# Driver_Board_Simplified.net
KiCad netlist of a schematic drawn in Altium Designer
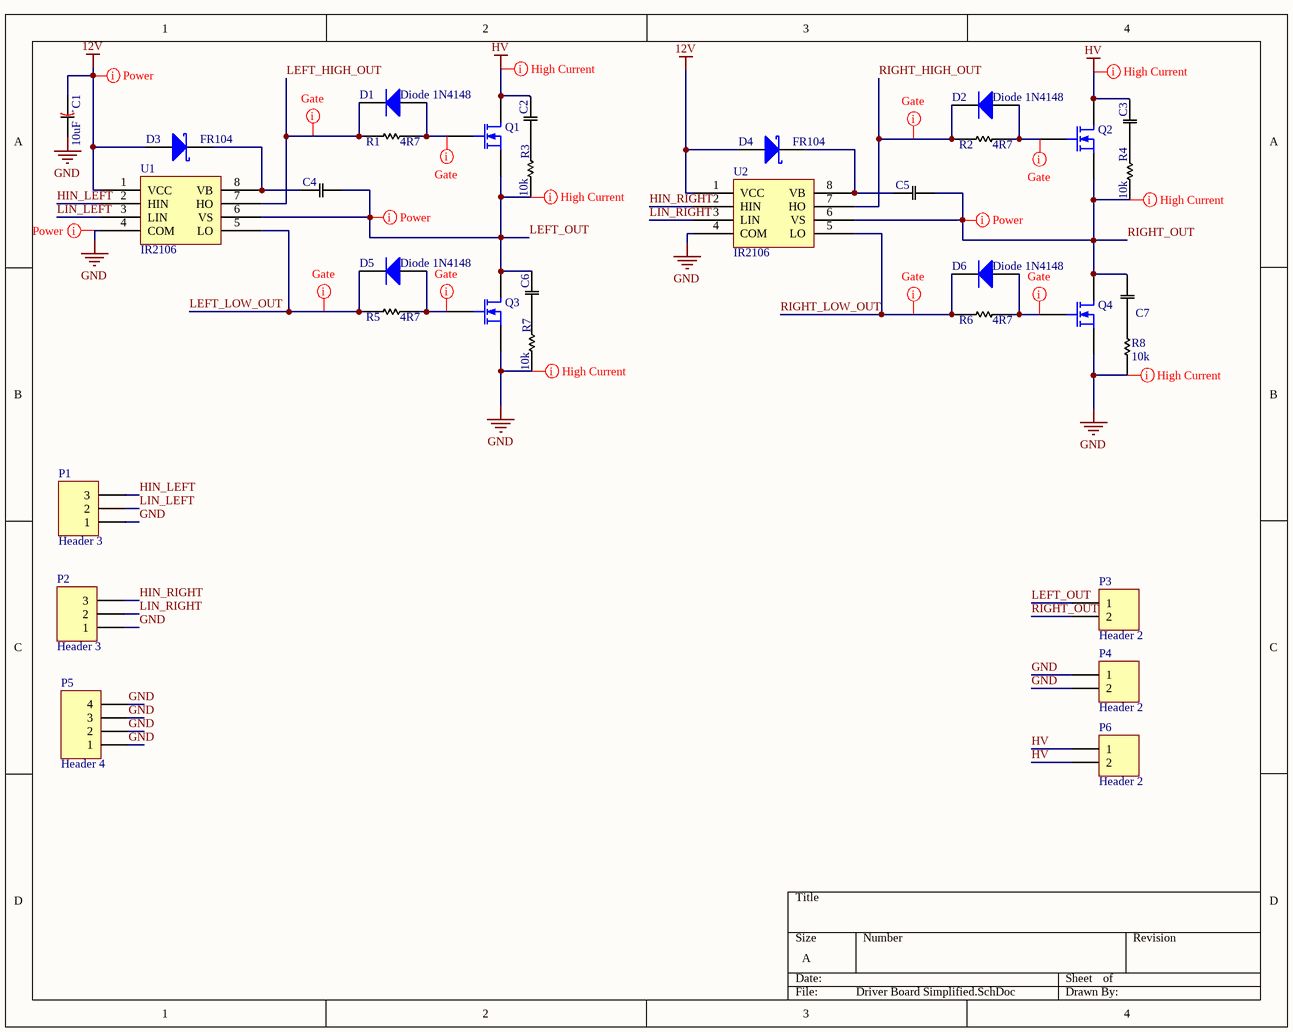
[diagram p0: Driver Board Simplified.SchDoc]

(export (version "E")
  (design (tool "Eeschema 10.0.6"))
  (components
    (comp (ref "C1")
      (value "10uF")
      (footprint "100mil CAP - 80mil pad")
      (libsource (lib "aroshaD") (part "Electrolytic Cap"))
    )
    (comp (ref "C2")
      (value "Ceramic Cap")
      (footprint "6-0805_N")
      (libsource (lib "aroshaD") (part "Ceramic Cap"))
    )
    (comp (ref "C3")
      (value "Ceramic Cap")
      (footprint "6-0805_N")
      (libsource (lib "aroshaD") (part "Ceramic Cap"))
    )
    (comp (ref "C4")
      (value "Ceramic Cap")
      (footprint "6-0805_L")
      (libsource (lib "aroshaD") (part "Ceramic Cap"))
    )
    (comp (ref "C5")
      (value "Ceramic Cap")
      (footprint "6-0805_L")
      (libsource (lib "aroshaD") (part "Ceramic Cap"))
    )
    (comp (ref "C6")
      (value "Ceramic Cap")
      (footprint "6-0805_N")
      (libsource (lib "aroshaD") (part "Ceramic Cap"))
    )
    (comp (ref "C7")
      (value "Ceramic Cap")
      (footprint "6-0805_N")
      (libsource (lib "aroshaD") (part "Ceramic Cap"))
    )
    (comp (ref "D1")
      (value "Diode 1N4148")
      (footprint "Resistor 100MIL")
      (description "High Conductance Fast Diode")
      (fields (field (name "PUBLISHER") "Altium Limited"))
      (libsource (lib "Miscellaneous Devices") (part "Diode 1N4148"))
    )
    (comp (ref "D2")
      (value "Diode 1N4148")
      (footprint "Resistor 100MIL")
      (description "High Conductance Fast Diode")
      (fields (field (name "PUBLISHER") "Altium Limited"))
      (libsource (lib "Miscellaneous Devices") (part "Diode 1N4148"))
    )
    (comp (ref "D3")
      (value "FR104")
      (footprint "DO-35")
      (description "Schottky Rectifier")
      (fields (field (name "PUBLISHER") "Altium Limited"))
      (libsource (lib "Miscellaneous Devices") (part "Diode 11DQ03"))
    )
    (comp (ref "D4")
      (value "FR104")
      (footprint "Resistor 100MIL")
      (description "Schottky Rectifier")
      (fields (field (name "PUBLISHER") "Altium Limited"))
      (libsource (lib "Miscellaneous Devices") (part "Diode 11DQ03"))
    )
    (comp (ref "D5")
      (value "Diode 1N4148")
      (footprint "Resistor 100MIL")
      (description "High Conductance Fast Diode")
      (fields (field (name "PUBLISHER") "Altium Limited"))
      (libsource (lib "Miscellaneous Devices") (part "Diode 1N4148"))
    )
    (comp (ref "D6")
      (value "Diode 1N4148")
      (footprint "Resistor 100MIL")
      (description "High Conductance Fast Diode")
      (fields (field (name "PUBLISHER") "Altium Limited"))
      (libsource (lib "Miscellaneous Devices") (part "Diode 1N4148"))
    )
    (comp (ref "P1")
      (value "Header 3")
      (footprint "HDR1X3")
      (description "Header, 3-Pin")
      (fields (field (name "PUBLISHER") "Altium Limited"))
      (libsource (lib "Miscellaneous Connectors") (part "Header 3"))
    )
    (comp (ref "P2")
      (value "Header 3")
      (footprint "HDR1X3")
      (description "Header, 3-Pin")
      (fields (field (name "PUBLISHER") "Altium Limited"))
      (libsource (lib "Miscellaneous Connectors") (part "Header 3"))
    )
    (comp (ref "P3")
      (value "Header 2")
      (footprint "2P_PCB_TERM_BLOCK_HDR")
      (description "Header, 2-Pin")
      (fields (field (name "PUBLISHER") "Altium Limited"))
      (libsource (lib "Miscellaneous Connectors") (part "Header 2"))
    )
    (comp (ref "P4")
      (value "Header 2")
      (footprint "2P_PCB_TERM_BLOCK_HDR")
      (description "Header, 2-Pin")
      (fields (field (name "PUBLISHER") "Altium Limited"))
      (libsource (lib "Miscellaneous Connectors") (part "Header 2"))
    )
    (comp (ref "P5")
      (value "Header 4")
      (footprint "HDR1X4")
      (description "Header, 4-Pin")
      (fields (field (name "PUBLISHER") "Altium Limited"))
      (libsource (lib "Miscellaneous Connectors") (part "Header 4"))
    )
    (comp (ref "P6")
      (value "Header 2")
      (footprint "2P_PCB_TERM_BLOCK_HDR")
      (description "Header, 2-Pin")
      (fields (field (name "PUBLISHER") "Altium Limited"))
      (libsource (lib "Miscellaneous Connectors") (part "Header 2"))
    )
    (comp (ref "Q1")
      (value "MOSFET-N")
      (footprint "TO-220AB")
      (description "N-Channel MOSFET")
      (fields (field (name "PUBLISHER") "Altium Limited"))
      (libsource (lib "Miscellaneous Devices") (part "MOSFET-N"))
    )
    (comp (ref "Q2")
      (value "MOSFET-N")
      (footprint "TO-220AB")
      (description "N-Channel MOSFET")
      (fields (field (name "PUBLISHER") "Altium Limited"))
      (libsource (lib "Miscellaneous Devices") (part "MOSFET-N"))
    )
    (comp (ref "Q3")
      (value "MOSFET-N")
      (footprint "TO-220AB")
      (description "N-Channel MOSFET")
      (fields (field (name "PUBLISHER") "Altium Limited"))
      (libsource (lib "Miscellaneous Devices") (part "MOSFET-N"))
    )
    (comp (ref "Q4")
      (value "MOSFET-N")
      (footprint "TO-220AB")
      (description "N-Channel MOSFET")
      (fields (field (name "PUBLISHER") "Altium Limited"))
      (libsource (lib "Miscellaneous Devices") (part "MOSFET-N"))
    )
    (comp (ref "R1")
      (value "4R7")
      (footprint "Resistor 100MIL")
      (libsource (lib "aroshaD") (part "Resistor"))
    )
    (comp (ref "R2")
      (value "4R7")
      (footprint "Resistor 100MIL")
      (libsource (lib "aroshaD") (part "Resistor"))
    )
    (comp (ref "R3") (value "10k") (footprint "6-0805_N") (libsource (lib "aroshaD") (part "Resistor")))
    (comp (ref "R4") (value "10k") (footprint "6-0805_N") (libsource (lib "aroshaD") (part "Resistor")))
    (comp (ref "R5")
      (value "4R7")
      (footprint "Resistor 100MIL")
      (libsource (lib "aroshaD") (part "Resistor"))
    )
    (comp (ref "R6")
      (value "4R7")
      (footprint "Resistor 100MIL")
      (libsource (lib "aroshaD") (part "Resistor"))
    )
    (comp (ref "R7") (value "10k") (footprint "6-0805_N") (libsource (lib "aroshaD") (part "Resistor")))
    (comp (ref "R8") (value "10k") (footprint "6-0805_N") (libsource (lib "aroshaD") (part "Resistor")))
    (comp (ref "U1") (value "IR2106") (footprint "SO8_N") (libsource (lib "aroshaD") (part "IR2106")))
    (comp (ref "U2") (value "IR2106") (footprint "SO8_N") (libsource (lib "aroshaD") (part "IR2106")))
  )
  (nets
    (net (code "1") (name "/HIN_LEFT") (class "Default")
      (node (ref "P1") (pin "3") (pinfunction "3_3") (pintype "passive"))
      (node (ref "U1") (pin "2") (pinfunction "HIN_2") (pintype "passive"))
    )
    (net (code "2") (name "/HIN_RIGHT") (class "Default")
      (node (ref "P2") (pin "3") (pinfunction "3_3") (pintype "passive"))
      (node (ref "U2") (pin "2") (pinfunction "HIN_2") (pintype "passive"))
    )
    (net (code "3") (name "/LEFT_HIGH_OUT") (class "Default")
      (node (ref "D1") (pin "2") (pinfunction "K_2") (pintype "passive"))
      (node (ref "R1") (pin "1") (pinfunction "6_1") (pintype "passive"))
      (node (ref "U1") (pin "7") (pinfunction "HO_7") (pintype "passive"))
    )
    (net (code "4") (name "/LEFT_LOW_OUT") (class "Default")
      (node (ref "D5") (pin "2") (pinfunction "K_2") (pintype "passive"))
      (node (ref "R5") (pin "1") (pinfunction "6_1") (pintype "passive"))
      (node (ref "U1") (pin "5") (pinfunction "LO_5") (pintype "passive"))
    )
    (net (code "5") (name "/LEFT_OUT") (class "Default")
      (node (ref "C4") (pin "1") (pinfunction "8_1") (pintype "passive"))
      (node (ref "C6") (pin "1") (pinfunction "8_1") (pintype "passive"))
      (node (ref "P3") (pin "1") (pinfunction "1_1") (pintype "passive"))
      (node (ref "Q1") (pin "3") (pinfunction "S_3") (pintype "passive"))
      (node (ref "Q3") (pin "1") (pinfunction "D_1") (pintype "passive"))
      (node (ref "R3") (pin "2") (pinfunction "7_2") (pintype "passive"))
      (node (ref "U1") (pin "6") (pinfunction "VS_6") (pintype "passive"))
    )
    (net (code "6") (name "/LIN_LEFT") (class "Default")
      (node (ref "P1") (pin "2") (pinfunction "2_2") (pintype "passive"))
      (node (ref "U1") (pin "3") (pinfunction "LIN_3") (pintype "passive"))
    )
    (net (code "7") (name "/LIN_RIGHT") (class "Default")
      (node (ref "P2") (pin "2") (pinfunction "2_2") (pintype "passive"))
      (node (ref "U2") (pin "3") (pinfunction "LIN_3") (pintype "passive"))
    )
    (net (code "8") (name "/RIGHT_HIGH_OUT") (class "Default")
      (node (ref "D2") (pin "2") (pinfunction "K_2") (pintype "passive"))
      (node (ref "R2") (pin "1") (pinfunction "6_1") (pintype "passive"))
      (node (ref "U2") (pin "7") (pinfunction "HO_7") (pintype "passive"))
    )
    (net (code "9") (name "/RIGHT_LOW_OUT") (class "Default")
      (node (ref "D6") (pin "2") (pinfunction "K_2") (pintype "passive"))
      (node (ref "R6") (pin "1") (pinfunction "6_1") (pintype "passive"))
      (node (ref "U2") (pin "5") (pinfunction "LO_5") (pintype "passive"))
    )
    (net (code "10") (name "/RIGHT_OUT") (class "Default")
      (node (ref "C5") (pin "1") (pinfunction "8_1") (pintype "passive"))
      (node (ref "C7") (pin "1") (pinfunction "8_1") (pintype "passive"))
      (node (ref "P3") (pin "2") (pinfunction "2_2") (pintype "passive"))
      (node (ref "Q2") (pin "3") (pinfunction "S_3") (pintype "passive"))
      (node (ref "Q4") (pin "1") (pinfunction "D_1") (pintype "passive"))
      (node (ref "R4") (pin "2") (pinfunction "7_2") (pintype "passive"))
      (node (ref "U2") (pin "6") (pinfunction "VS_6") (pintype "passive"))
    )
    (net (code "11") (name "12V") (class "Default")
      (node (ref "C1") (pin "1") (pinfunction "8_1") (pintype "passive"))
      (node (ref "D3") (pin "1") (pinfunction "A_1") (pintype "passive"))
      (node (ref "D4") (pin "1") (pinfunction "A_1") (pintype "passive"))
      (node (ref "U1") (pin "1") (pinfunction "VCC_1") (pintype "passive"))
      (node (ref "U2") (pin "1") (pinfunction "VCC_1") (pintype "passive"))
    )
    (net (code "12") (name "GND") (class "Default")
      (node (ref "C1") (pin "2") (pinfunction "9_2") (pintype "passive"))
      (node (ref "P1") (pin "1") (pinfunction "1_1") (pintype "passive"))
      (node (ref "P2") (pin "1") (pinfunction "1_1") (pintype "passive"))
      (node (ref "P4") (pin "1") (pinfunction "1_1") (pintype "passive"))
      (node (ref "P4") (pin "2") (pinfunction "2_2") (pintype "passive"))
      (node (ref "P5") (pin "1") (pinfunction "1_1") (pintype "passive"))
      (node (ref "P5") (pin "2") (pinfunction "2_2") (pintype "passive"))
      (node (ref "P5") (pin "3") (pinfunction "3_3") (pintype "passive"))
      (node (ref "P5") (pin "4") (pinfunction "4_4") (pintype "passive"))
      (node (ref "Q3") (pin "3") (pinfunction "S_3") (pintype "passive"))
      (node (ref "Q4") (pin "3") (pinfunction "S_3") (pintype "passive"))
      (node (ref "R7") (pin "2") (pinfunction "7_2") (pintype "passive"))
      (node (ref "R8") (pin "2") (pinfunction "7_2") (pintype "passive"))
      (node (ref "U1") (pin "4") (pinfunction "COM_4") (pintype "passive"))
      (node (ref "U2") (pin "4") (pinfunction "COM_4") (pintype "passive"))
    )
    (net (code "13") (name "HV") (class "Default")
      (node (ref "C2") (pin "1") (pinfunction "8_1") (pintype "passive"))
      (node (ref "C3") (pin "1") (pinfunction "8_1") (pintype "passive"))
      (node (ref "P6") (pin "1") (pinfunction "1_1") (pintype "passive"))
      (node (ref "P6") (pin "2") (pinfunction "2_2") (pintype "passive"))
      (node (ref "Q1") (pin "1") (pinfunction "D_1") (pintype "passive"))
      (node (ref "Q2") (pin "1") (pinfunction "D_1") (pintype "passive"))
    )
    (net (code "14") (name "Net-(C2-9)") (class "Default")
      (node (ref "C2") (pin "2") (pinfunction "9_2") (pintype "passive"))
      (node (ref "R3") (pin "1") (pinfunction "6_1") (pintype "passive"))
    )
    (net (code "15") (name "Net-(C3-9)") (class "Default")
      (node (ref "C3") (pin "2") (pinfunction "9_2") (pintype "passive"))
      (node (ref "R4") (pin "1") (pinfunction "6_1") (pintype "passive"))
    )
    (net (code "16") (name "Net-(C4-9)") (class "Default")
      (node (ref "C4") (pin "2") (pinfunction "9_2") (pintype "passive"))
      (node (ref "D3") (pin "2") (pinfunction "K_2") (pintype "passive"))
      (node (ref "U1") (pin "8") (pinfunction "VB_8") (pintype "passive"))
    )
    (net (code "17") (name "Net-(C5-9)") (class "Default")
      (node (ref "C5") (pin "2") (pinfunction "9_2") (pintype "passive"))
      (node (ref "D4") (pin "2") (pinfunction "K_2") (pintype "passive"))
      (node (ref "U2") (pin "8") (pinfunction "VB_8") (pintype "passive"))
    )
    (net (code "18") (name "Net-(C6-9)") (class "Default")
      (node (ref "C6") (pin "2") (pinfunction "9_2") (pintype "passive"))
      (node (ref "R7") (pin "1") (pinfunction "6_1") (pintype "passive"))
    )
    (net (code "19") (name "Net-(C7-9)") (class "Default")
      (node (ref "C7") (pin "2") (pinfunction "9_2") (pintype "passive"))
      (node (ref "R8") (pin "1") (pinfunction "6_1") (pintype "passive"))
    )
    (net (code "20") (name "Net-(D1-A)") (class "Default")
      (node (ref "D1") (pin "1") (pinfunction "A_1") (pintype "passive"))
      (node (ref "Q1") (pin "2") (pinfunction "G_2") (pintype "passive"))
      (node (ref "R1") (pin "2") (pinfunction "7_2") (pintype "passive"))
    )
    (net (code "21") (name "Net-(D2-A)") (class "Default")
      (node (ref "D2") (pin "1") (pinfunction "A_1") (pintype "passive"))
      (node (ref "Q2") (pin "2") (pinfunction "G_2") (pintype "passive"))
      (node (ref "R2") (pin "2") (pinfunction "7_2") (pintype "passive"))
    )
    (net (code "22") (name "Net-(D5-A)") (class "Default")
      (node (ref "D5") (pin "1") (pinfunction "A_1") (pintype "passive"))
      (node (ref "Q3") (pin "2") (pinfunction "G_2") (pintype "passive"))
      (node (ref "R5") (pin "2") (pinfunction "7_2") (pintype "passive"))
    )
    (net (code "23") (name "Net-(D6-A)") (class "Default")
      (node (ref "D6") (pin "1") (pinfunction "A_1") (pintype "passive"))
      (node (ref "Q4") (pin "2") (pinfunction "G_2") (pintype "passive"))
      (node (ref "R6") (pin "2") (pinfunction "7_2") (pintype "passive"))
    )
  )
)
